# design.net
KiCad netlist of a schematic drawn in Altium Designer
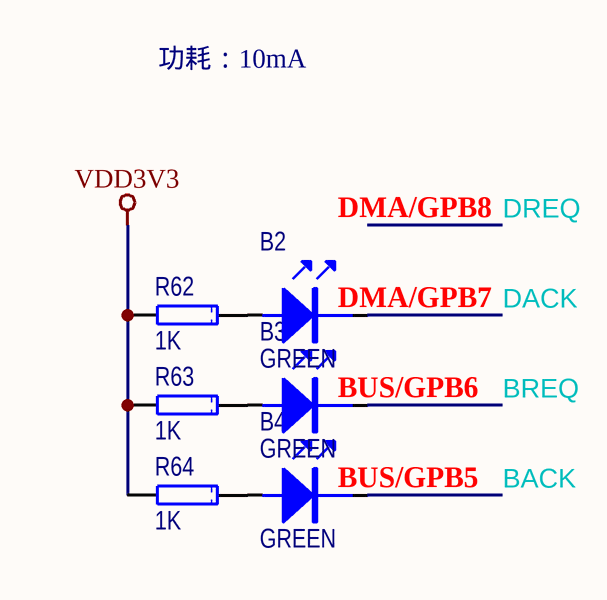
[diagram p0: 指示灯.SchDoc]

(export (version "E")
  (design (tool "Eeschema 10.0.6"))
  (components
    (comp (ref "B2")
      (value "GREEN")
      (footprint "0805LED")
      (description "发光管")
      (libsource (lib "*") (part "LED"))
    )
    (comp (ref "B3")
      (value "GREEN")
      (footprint "0805LED")
      (description "发光管")
      (libsource (lib "*") (part "LED"))
    )
    (comp (ref "B4")
      (value "GREEN")
      (footprint "0805LED")
      (description "发光管")
      (libsource (lib "*") (part "LED"))
    )
    (comp (ref "R62")
      (value "1K")
      (footprint "1608[0603]R")
      (description "RES")
      (fields (field (name "MANUFACTURER") "vishay"))
      (libsource (lib "*") (part "RES"))
    )
    (comp (ref "R63")
      (value "1K")
      (footprint "1608[0603]R")
      (description "RES")
      (fields (field (name "MANUFACTURER") "vishay"))
      (libsource (lib "*") (part "RES"))
    )
    (comp (ref "R64")
      (value "1K")
      (footprint "1608[0603]R")
      (description "RES")
      (fields (field (name "MANUFACTURER") "vishay"))
      (libsource (lib "*") (part "RES"))
    )
  )
  (nets
    (net (code "1") (name "/BACK") (class "Default")
      (node (ref "B4") (pin "2") (pinfunction "2_2") (pintype "passive"))
    )
    (net (code "2") (name "/BREQ") (class "Default")
      (node (ref "B3") (pin "2") (pinfunction "2_2") (pintype "passive"))
    )
    (net (code "3") (name "/DACK") (class "Default")
      (node (ref "B2") (pin "2") (pinfunction "2_2") (pintype "passive"))
    )
    (net (code "5") (name "Net-(B2-Pad1)") (class "Default")
      (node (ref "B2") (pin "1") (pinfunction "1_1") (pintype "passive"))
      (node (ref "R62") (pin "1") (pinfunction "1_1") (pintype "passive"))
    )
    (net (code "6") (name "Net-(B3-Pad1)") (class "Default")
      (node (ref "B3") (pin "1") (pinfunction "1_1") (pintype "passive"))
      (node (ref "R63") (pin "1") (pinfunction "1_1") (pintype "passive"))
    )
    (net (code "7") (name "Net-(B4-Pad1)") (class "Default")
      (node (ref "B4") (pin "1") (pinfunction "1_1") (pintype "passive"))
      (node (ref "R64") (pin "1") (pinfunction "1_1") (pintype "passive"))
    )
    (net (code "8") (name "VDD3V3") (class "Default")
      (node (ref "R62") (pin "2") (pinfunction "2_2") (pintype "passive"))
      (node (ref "R63") (pin "2") (pinfunction "2_2") (pintype "passive"))
      (node (ref "R64") (pin "2") (pinfunction "2_2") (pintype "passive"))
    )
  )
)
